# Bandpass.net
KiCad netlist of a schematic drawn in Altium Designer
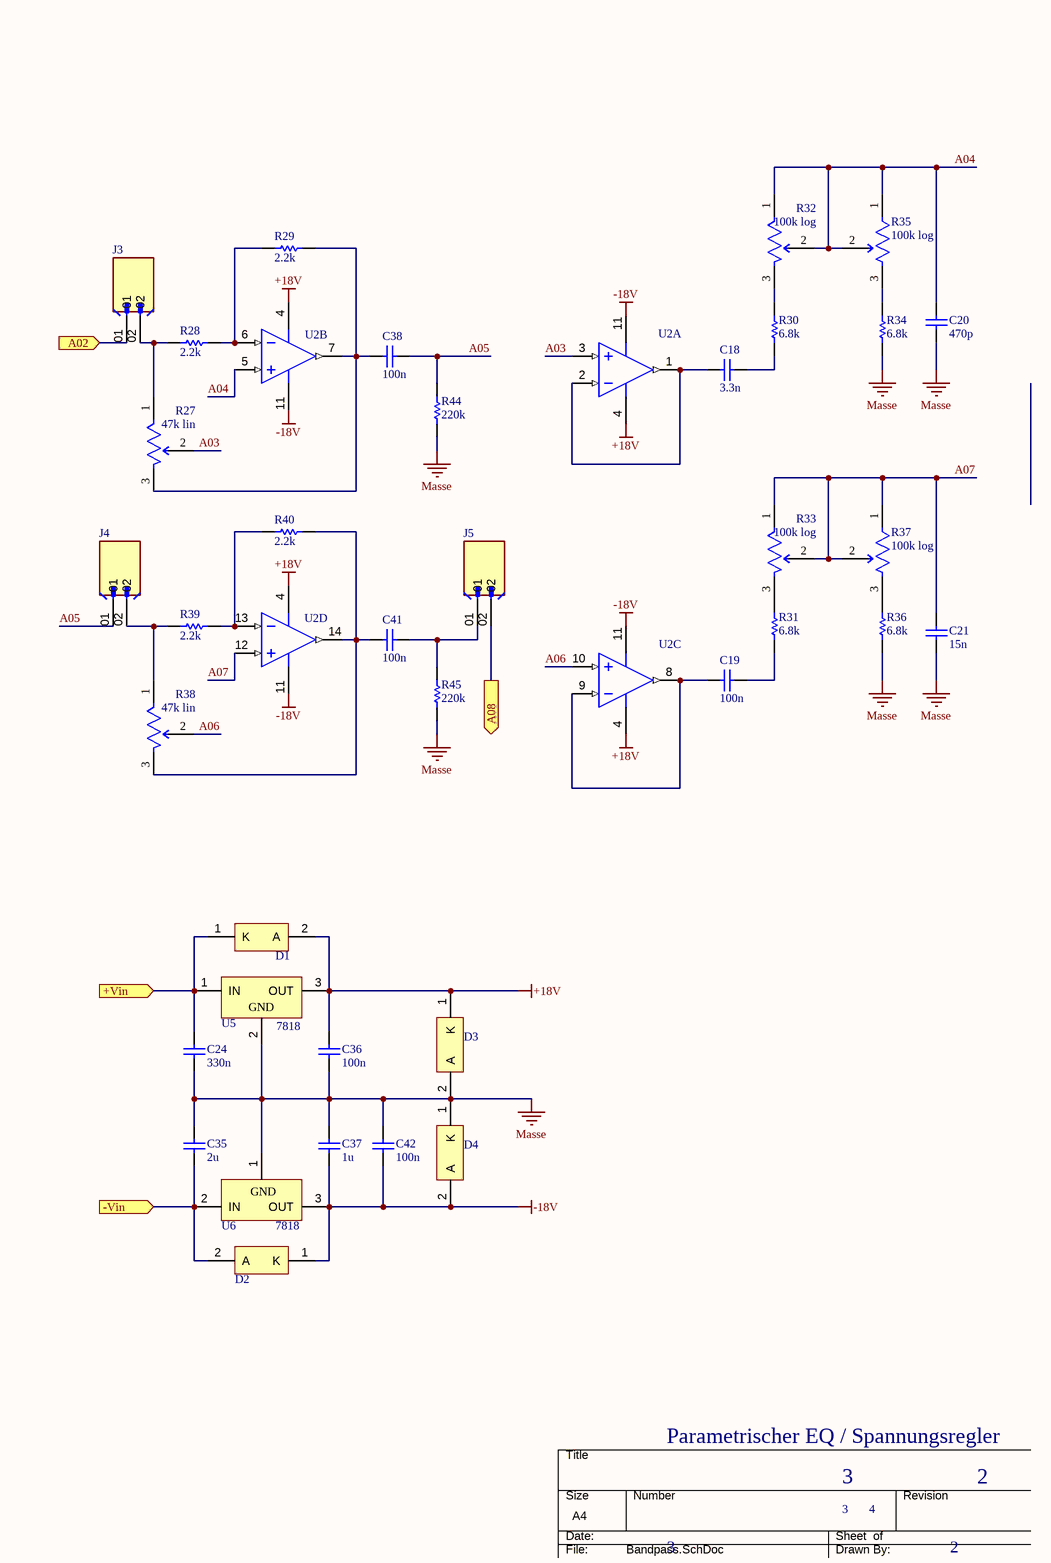
[diagram p0: Bandpass.SchDoc]

(export (version "E")
  (design (tool "Eeschema 10.0.6"))
  (components
    (comp (ref "C18")
      (value "3.3n")
      (footprint "0805")
      (description "0805 Kondensator")
      (libsource (lib "Bauteile") (part "0805 Kondensator"))
    )
    (comp (ref "C19")
      (value "100n")
      (footprint "0805")
      (description "0805 Kondensator")
      (libsource (lib "Bauteile") (part "0805 Kondensator"))
    )
    (comp (ref "C20")
      (value "470p")
      (footprint "0805")
      (description "0805 Kondensator")
      (libsource (lib "Bauteile") (part "0805 Kondensator"))
    )
    (comp (ref "C21")
      (value "15n")
      (footprint "0805")
      (description "0805 Kondensator")
      (libsource (lib "Bauteile") (part "0805 Kondensator"))
    )
    (comp (ref "C24")
      (value "330n")
      (footprint "0805")
      (description "0805 Kondensator")
      (libsource (lib "Bauteile") (part "0805 Kondensator"))
    )
    (comp (ref "C35")
      (value "2u")
      (footprint "0805")
      (description "0805 Kondensator")
      (libsource (lib "Bauteile") (part "0805 Kondensator"))
    )
    (comp (ref "C36")
      (value "100n")
      (footprint "0805")
      (description "0805 Kondensator")
      (libsource (lib "Bauteile") (part "0805 Kondensator"))
    )
    (comp (ref "C37")
      (value "1u")
      (footprint "0805")
      (description "0805 Kondensator")
      (libsource (lib "Bauteile") (part "0805 Kondensator"))
    )
    (comp (ref "C38")
      (value "100n")
      (footprint "0805")
      (description "0805 Kondensator")
      (libsource (lib "Bauteile") (part "0805 Kondensator"))
    )
    (comp (ref "C41")
      (value "100n")
      (footprint "0805")
      (description "0805 Kondensator")
      (libsource (lib "Bauteile") (part "0805 Kondensator"))
    )
    (comp (ref "C42")
      (value "100n")
      (footprint "0805")
      (description "0805 Kondensator")
      (libsource (lib "Bauteile") (part "0805 Kondensator"))
    )
    (comp (ref "D1")
      (value "1N4001 Diode")
      (footprint "1N4001 Diode")
      (description "Standard Recovery Rectifier, 2-Pin Axial_Lead, Pb-Free, Bulk Bag")
      (fields (field (name "PARTNUMBER") "1N4001") (field (name "MANUFACTURER") "On Semiconductor"))
      (libsource (lib "Bauteile") (part "1N4001 Diode"))
    )
    (comp (ref "D2")
      (value "1N4001 Diode")
      (footprint "1N4001 Diode")
      (description "Standard Recovery Rectifier, 2-Pin Axial_Lead, Pb-Free, Bulk Bag")
      (fields (field (name "PARTNUMBER") "1N4001") (field (name "MANUFACTURER") "On Semiconductor"))
      (libsource (lib "") (part "1N4001 Diode_2"))
    )
    (comp (ref "D3")
      (value "1N4001 Diode")
      (footprint "1N4001 Diode")
      (description "Standard Recovery Rectifier, 2-Pin Axial_Lead, Pb-Free, Bulk Bag")
      (fields (field (name "PARTNUMBER") "1N4001") (field (name "MANUFACTURER") "On Semiconductor"))
      (libsource (lib "") (part "1N4001 Diode_1"))
    )
    (comp (ref "D4")
      (value "1N4001 Diode")
      (footprint "1N4001 Diode")
      (description "Standard Recovery Rectifier, 2-Pin Axial_Lead, Pb-Free, Bulk Bag")
      (fields (field (name "PARTNUMBER") "1N4001") (field (name "MANUFACTURER") "On Semiconductor"))
      (libsource (lib "") (part "1N4001 Diode_1"))
    )
    (comp (ref "J3")
      (value "Connector x2")
      (footprint "Connector x2")
      (description "Connector Header Through Hole 2 position 0.100 (2.54mm)")
      (fields (field (name "MF") "Wurth Elektronik") (field (name "MP") "61300211121"))
      (libsource (lib "Bauteile") (part "Connector x2"))
    )
    (comp (ref "J4")
      (value "Connector x2")
      (footprint "Connector x2")
      (description "Connector Header Through Hole 2 position 0.100 (2.54mm)")
      (fields (field (name "MF") "Wurth Elektronik") (field (name "MP") "61300211121"))
      (libsource (lib "Bauteile") (part "Connector x2"))
    )
    (comp (ref "J5")
      (value "Connector x2")
      (footprint "Connector x2")
      (description "Connector Header Through Hole 2 position 0.100 (2.54mm)")
      (fields (field (name "MF") "Wurth Elektronik") (field (name "MP") "61300211121"))
      (libsource (lib "Bauteile") (part "Connector x2"))
    )
    (comp (ref "R27")
      (value "47k lin")
      (footprint "Connector x3")
      (description "Potentiometer")
      (libsource (lib "Bauteile") (part "Potentiometer Buchsenleiste"))
    )
    (comp (ref "R28")
      (value "2.2k")
      (footprint "0805")
      (description "0805 Widerstand")
      (libsource (lib "Bauteile") (part "0805 Widerstand"))
    )
    (comp (ref "R29")
      (value "2.2k")
      (footprint "0805")
      (description "0805 Widerstand")
      (libsource (lib "Bauteile") (part "0805 Widerstand"))
    )
    (comp (ref "R30")
      (value "6.8k")
      (footprint "0805")
      (description "0805 Widerstand")
      (libsource (lib "Bauteile") (part "0805 Widerstand"))
    )
    (comp (ref "R31")
      (value "6.8k")
      (footprint "0805")
      (description "0805 Widerstand")
      (libsource (lib "Bauteile") (part "0805 Widerstand"))
    )
    (comp (ref "R32")
      (value "100k log")
      (footprint "Connector x3")
      (description "Potentiometer")
      (libsource (lib "Bauteile") (part "Potentiometer Buchsenleiste"))
    )
    (comp (ref "R33")
      (value "100k log")
      (footprint "Connector x3")
      (description "Potentiometer")
      (libsource (lib "Bauteile") (part "Potentiometer Buchsenleiste"))
    )
    (comp (ref "R34")
      (value "6.8k")
      (footprint "0805")
      (description "0805 Widerstand")
      (libsource (lib "Bauteile") (part "0805 Widerstand"))
    )
    (comp (ref "R35")
      (value "100k log")
      (footprint "Connector x3")
      (description "Potentiometer")
      (libsource (lib "Bauteile") (part "Potentiometer Buchsenleiste"))
    )
    (comp (ref "R36")
      (value "6.8k")
      (footprint "0805")
      (description "0805 Widerstand")
      (libsource (lib "Bauteile") (part "0805 Widerstand"))
    )
    (comp (ref "R37")
      (value "100k log")
      (footprint "Connector x3")
      (description "Potentiometer")
      (libsource (lib "Bauteile") (part "Potentiometer Buchsenleiste"))
    )
    (comp (ref "R38")
      (value "47k lin")
      (footprint "Connector x3")
      (description "Potentiometer")
      (libsource (lib "Bauteile") (part "Potentiometer Buchsenleiste"))
    )
    (comp (ref "R39")
      (value "2.2k")
      (footprint "0805")
      (description "0805 Widerstand")
      (libsource (lib "Bauteile") (part "0805 Widerstand"))
    )
    (comp (ref "R40")
      (value "2.2k")
      (footprint "0805")
      (description "0805 Widerstand")
      (libsource (lib "Bauteile") (part "0805 Widerstand"))
    )
    (comp (ref "R44")
      (value "220k")
      (footprint "0805")
      (description "0805 Widerstand")
      (libsource (lib "Bauteile") (part "0805 Widerstand"))
    )
    (comp (ref "R45")
      (value "220k")
      (footprint "0805")
      (description "0805 Widerstand")
      (libsource (lib "Bauteile") (part "0805 Widerstand"))
    )
    (comp (ref "U2")
      (value "OPA4134UA")
      (footprint "DIP14 IC Socket")
      (fields (field (name "MANUFACTURER") "Texas Instruments"))
      (libsource (lib "Bauteile") (part "SOIC OPA4134UA"))
    )
    (comp (ref "U5")
      (value "7818")
      (footprint "TO220 Spannungsregler 78xx")
      (description "Voltage Regulator, 3-Pin TO-220")
      (libsource (lib "Bauteile") (part "TO 220 Spannungsregler 78xx"))
    )
    (comp (ref "U6")
      (value "7818")
      (footprint "TO220 Spannungsregler 79xx")
      (description "Voltage Regulator, 3-Pin TO-220")
      (libsource (lib "Bauteile") (part "TO 220 Spannungsregler 79xx"))
    )
  )
  (nets
    (net (code "1") (name "+18V") (class "Default")
      (node (ref "C36") (pin "2") (pinfunction "2_2") (pintype "passive"))
      (node (ref "D1") (pin "2") (pinfunction "A_2") (pintype "passive"))
      (node (ref "D3") (pin "1") (pinfunction "K_1") (pintype "passive"))
      (node (ref "U2") (pin "4") (pinfunction "V+_4") (pintype "power_in"))
      (node (ref "U5") (pin "3") (pinfunction "OUT_3") (pintype "power_in"))
    )
    (net (code "2") (name "-18V") (class "Default")
      (node (ref "C37") (pin "2") (pinfunction "2_2") (pintype "passive"))
      (node (ref "C42") (pin "1") (pinfunction "1_1") (pintype "passive"))
      (node (ref "D2") (pin "1") (pinfunction "K_1") (pintype "passive"))
      (node (ref "D4") (pin "2") (pinfunction "A_2") (pintype "passive"))
      (node (ref "U2") (pin "11") (pinfunction "V-_11") (pintype "power_in"))
      (node (ref "U6") (pin "3") (pinfunction "OUT_3") (pintype "power_in"))
    )
    (net (code "3") (name "/+Vin") (class "Default")
      (node (ref "C24") (pin "2") (pinfunction "2_2") (pintype "passive"))
      (node (ref "D1") (pin "1") (pinfunction "K_1") (pintype "passive"))
      (node (ref "U5") (pin "1") (pinfunction "IN_1") (pintype "passive"))
    )
    (net (code "4") (name "/-Vin") (class "Default")
      (node (ref "C35") (pin "2") (pinfunction "2_2") (pintype "passive"))
      (node (ref "D2") (pin "2") (pinfunction "A_2") (pintype "passive"))
      (node (ref "U6") (pin "2") (pinfunction "IN_2") (pintype "passive"))
    )
    (net (code "5") (name "/A02") (class "Default")
      (node (ref "J3") (pin "01") (pinfunction "01_01") (pintype "passive"))
    )
    (net (code "6") (name "/A03") (class "Default")
      (node (ref "R27") (pin "2") (pinfunction "b_2") (pintype "passive"))
      (node (ref "U2") (pin "3") (pinfunction "IN_A+_3") (pintype "input"))
    )
    (net (code "7") (name "/A04") (class "Default")
      (node (ref "C20") (pin "2") (pinfunction "2_2") (pintype "passive"))
      (node (ref "R32") (pin "1") (pinfunction "a_1") (pintype "passive"))
      (node (ref "R32") (pin "2") (pinfunction "b_2") (pintype "passive"))
      (node (ref "R35") (pin "1") (pinfunction "a_1") (pintype "passive"))
      (node (ref "R35") (pin "2") (pinfunction "b_2") (pintype "passive"))
      (node (ref "U2") (pin "5") (pinfunction "IN_B+_5") (pintype "input"))
    )
    (net (code "8") (name "/A05") (class "Default")
      (node (ref "C38") (pin "2") (pinfunction "2_2") (pintype "passive"))
      (node (ref "J4") (pin "01") (pinfunction "01_01") (pintype "passive"))
      (node (ref "R44") (pin "2") (pinfunction "2_2") (pintype "passive"))
    )
    (net (code "9") (name "/A06") (class "Default")
      (node (ref "R38") (pin "2") (pinfunction "b_2") (pintype "passive"))
      (node (ref "U2") (pin "10") (pinfunction "IN_C+_10") (pintype "input"))
    )
    (net (code "10") (name "/A07") (class "Default")
      (node (ref "C21") (pin "1") (pinfunction "1_1") (pintype "passive"))
      (node (ref "R33") (pin "1") (pinfunction "a_1") (pintype "passive"))
      (node (ref "R33") (pin "2") (pinfunction "b_2") (pintype "passive"))
      (node (ref "R37") (pin "1") (pinfunction "a_1") (pintype "passive"))
      (node (ref "R37") (pin "2") (pinfunction "b_2") (pintype "passive"))
      (node (ref "U2") (pin "12") (pinfunction "IN_D+_12") (pintype "input"))
    )
    (net (code "11") (name "/A08") (class "Default")
      (node (ref "J5") (pin "02") (pinfunction "02_02") (pintype "passive"))
    )
    (net (code "12") (name "Masse") (class "Default")
      (node (ref "C20") (pin "1") (pinfunction "1_1") (pintype "passive"))
      (node (ref "C21") (pin "2") (pinfunction "2_2") (pintype "passive"))
      (node (ref "C24") (pin "1") (pinfunction "1_1") (pintype "passive"))
      (node (ref "C35") (pin "1") (pinfunction "1_1") (pintype "passive"))
      (node (ref "C36") (pin "1") (pinfunction "1_1") (pintype "passive"))
      (node (ref "C37") (pin "1") (pinfunction "1_1") (pintype "passive"))
      (node (ref "C42") (pin "2") (pinfunction "2_2") (pintype "passive"))
      (node (ref "D3") (pin "2") (pinfunction "A_2") (pintype "passive"))
      (node (ref "D4") (pin "1") (pinfunction "K_1") (pintype "passive"))
      (node (ref "R34") (pin "1") (pinfunction "1_1") (pintype "passive"))
      (node (ref "R36") (pin "2") (pinfunction "2_2") (pintype "passive"))
      (node (ref "R44") (pin "1") (pinfunction "1_1") (pintype "passive"))
      (node (ref "R45") (pin "1") (pinfunction "1_1") (pintype "passive"))
      (node (ref "U5") (pin "2") (pinfunction "GND_2") (pintype "power_in"))
      (node (ref "U6") (pin "1") (pinfunction "GND_1") (pintype "power_in"))
    )
    (net (code "13") (name "Net-(C18-Pad2)") (class "Default")
      (node (ref "C18") (pin "2") (pinfunction "2_2") (pintype "passive"))
      (node (ref "R30") (pin "1") (pinfunction "1_1") (pintype "passive"))
    )
    (net (code "14") (name "Net-(C19-Pad1)") (class "Default")
      (node (ref "C19") (pin "1") (pinfunction "1_1") (pintype "passive"))
      (node (ref "R31") (pin "2") (pinfunction "2_2") (pintype "passive"))
    )
    (net (code "15") (name "Net-(C41-Pad2)") (class "Default")
      (node (ref "C41") (pin "2") (pinfunction "2_2") (pintype "passive"))
      (node (ref "J5") (pin "01") (pinfunction "01_01") (pintype "passive"))
      (node (ref "R45") (pin "2") (pinfunction "2_2") (pintype "passive"))
    )
    (net (code "16") (name "Net-(R27-a)") (class "Default")
      (node (ref "J3") (pin "02") (pinfunction "02_02") (pintype "passive"))
      (node (ref "R27") (pin "1") (pinfunction "a_1") (pintype "passive"))
      (node (ref "R28") (pin "1") (pinfunction "1_1") (pintype "passive"))
    )
    (net (code "17") (name "Net-(R27-c)") (class "Default")
      (node (ref "C38") (pin "1") (pinfunction "1_1") (pintype "passive"))
      (node (ref "R27") (pin "3") (pinfunction "c_3") (pintype "passive"))
      (node (ref "R29") (pin "2") (pinfunction "2_2") (pintype "passive"))
      (node (ref "U2") (pin "7") (pinfunction "OUT_B_7") (pintype "output"))
    )
    (net (code "18") (name "Net-(R32-c)") (class "Default")
      (node (ref "R30") (pin "2") (pinfunction "2_2") (pintype "passive"))
      (node (ref "R32") (pin "3") (pinfunction "c_3") (pintype "passive"))
    )
    (net (code "19") (name "Net-(R33-c)") (class "Default")
      (node (ref "R31") (pin "1") (pinfunction "1_1") (pintype "passive"))
      (node (ref "R33") (pin "3") (pinfunction "c_3") (pintype "passive"))
    )
    (net (code "20") (name "Net-(R35-c)") (class "Default")
      (node (ref "R34") (pin "2") (pinfunction "2_2") (pintype "passive"))
      (node (ref "R35") (pin "3") (pinfunction "c_3") (pintype "passive"))
    )
    (net (code "21") (name "Net-(R37-c)") (class "Default")
      (node (ref "R36") (pin "1") (pinfunction "1_1") (pintype "passive"))
      (node (ref "R37") (pin "3") (pinfunction "c_3") (pintype "passive"))
    )
    (net (code "22") (name "Net-(R38-a)") (class "Default")
      (node (ref "J4") (pin "02") (pinfunction "02_02") (pintype "passive"))
      (node (ref "R38") (pin "1") (pinfunction "a_1") (pintype "passive"))
      (node (ref "R39") (pin "1") (pinfunction "1_1") (pintype "passive"))
    )
    (net (code "23") (name "Net-(R38-c)") (class "Default")
      (node (ref "C41") (pin "1") (pinfunction "1_1") (pintype "passive"))
      (node (ref "R38") (pin "3") (pinfunction "c_3") (pintype "passive"))
      (node (ref "R40") (pin "2") (pinfunction "2_2") (pintype "passive"))
      (node (ref "U2") (pin "14") (pinfunction "OUT_D_14") (pintype "output"))
    )
    (net (code "24") (name "Net-(U2A-IN_A-)") (class "Default")
      (node (ref "C18") (pin "1") (pinfunction "1_1") (pintype "passive"))
      (node (ref "U2") (pin "1") (pinfunction "OUT_A_1") (pintype "output"))
      (node (ref "U2") (pin "2") (pinfunction "IN_A-_2") (pintype "input"))
    )
    (net (code "25") (name "Net-(U2B-IN_B-)") (class "Default")
      (node (ref "R28") (pin "2") (pinfunction "2_2") (pintype "passive"))
      (node (ref "R29") (pin "1") (pinfunction "1_1") (pintype "passive"))
      (node (ref "U2") (pin "6") (pinfunction "IN_B-_6") (pintype "input"))
    )
    (net (code "26") (name "Net-(U2C-IN_C-)") (class "Default")
      (node (ref "C19") (pin "2") (pinfunction "2_2") (pintype "passive"))
      (node (ref "U2") (pin "8") (pinfunction "OUT_C_8") (pintype "output"))
      (node (ref "U2") (pin "9") (pinfunction "IN_C-_9") (pintype "input"))
    )
    (net (code "27") (name "Net-(U2D-IN_D-)") (class "Default")
      (node (ref "R39") (pin "2") (pinfunction "2_2") (pintype "passive"))
      (node (ref "R40") (pin "1") (pinfunction "1_1") (pintype "passive"))
      (node (ref "U2") (pin "13") (pinfunction "IN_D-_13") (pintype "input"))
    )
  )
)
